# Heater_Control.net
KiCad netlist of a schematic drawn in Altium Designer
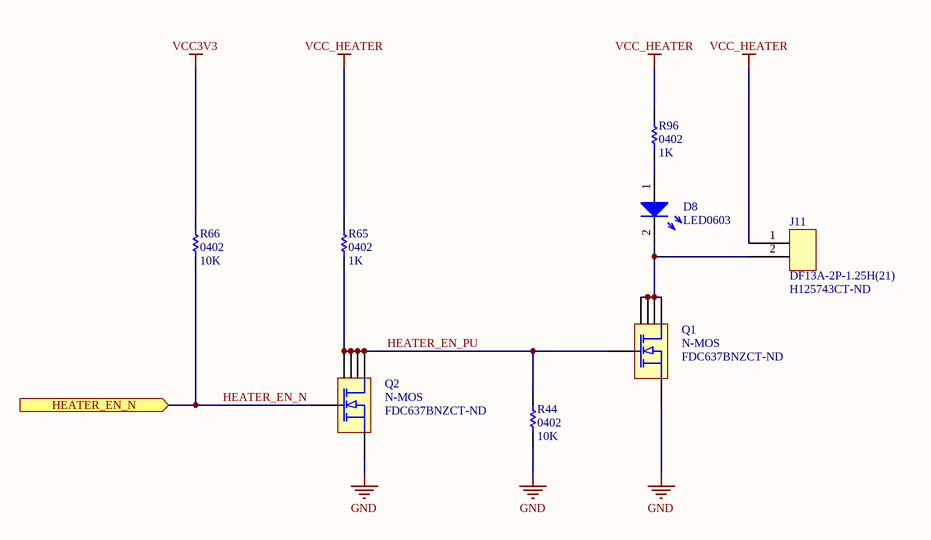
[diagram p0: Heater Control.SchDoc]

(export (version "E")
  (design (tool "Eeschema 10.0.6"))
  (components
    (comp (ref "D8")
      (value "LED0603")
      (footprint "LED0603")
      (description "Generic 0603 LED. Use ChipLED from Osram for generic ones.")
      (libsource (lib "heron-general") (part "LED0603"))
    )
    (comp (ref "J11")
      (value "DF13A-2P-1.25H(21)")
      (footprint "DF13A-2P-1.25H(21)")
      (description "2 pos DF13 right angle surface mount connector")
      (fields (field (name "SUPPLIER PART NUMBER 1") "H125743CT-ND"))
      (libsource (lib "DF13A-2P-1.25H(21)") (part "DF13A-2P-1.25H(21)"))
    )
    (comp (ref "Q1")
      (value "N-MOS")
      (footprint "SOT95P280X145-6N")
      (description "20V 6.2A, N-MOS, low gate on voltage")
      (fields (field (name "SUPPLIER PART NUMBER 1") "FDC637BNZCT-ND"))
      (libsource (lib "heron-general") (part "FDC637BNZCT-ND"))
    )
    (comp (ref "Q2")
      (value "N-MOS")
      (footprint "SOT95P280X145-6N")
      (description "20V 6.2A, N-MOS, low gate on voltage")
      (fields (field (name "SUPPLIER PART NUMBER 1") "FDC637BNZCT-ND"))
      (libsource (lib "heron-general") (part "FDC637BNZCT-ND"))
    )
    (comp (ref "R44")
      (value "0402")
      (footprint "RES0402R")
      (description "0402 resistor")
      (fields
        (field (name "ALTIUM_VALUE") "10K")
        (field (name "MANUFACTURER") "Panasonic")
        (field (name "MANUFACTURER PART NUMBER") "ERJ-2RKF1002X")
      )
      (libsource (lib "heron-general") (part "RES0402"))
    )
    (comp (ref "R65")
      (value "0402")
      (footprint "RES0402R")
      (description "0402 resistor")
      (fields (field (name "ALTIUM_VALUE") "1K"))
      (libsource (lib "RES0402") (part "RES0402"))
    )
    (comp (ref "R66")
      (value "0402")
      (footprint "RES0402R")
      (description "0402 resistor")
      (fields
        (field (name "ALTIUM_VALUE") "10K")
        (field (name "MANUFACTURER") "Panasonic")
        (field (name "MANUFACTURER PART NUMBER") "ERJ-2RKF1002X")
      )
      (libsource (lib "heron-general") (part "RES0402"))
    )
    (comp (ref "R96")
      (value "0402")
      (footprint "RES0402R")
      (description "0402 resistor")
      (fields (field (name "ALTIUM_VALUE") "1K"))
      (libsource (lib "RES0402") (part "RES0402"))
    )
  )
  (nets
    (net (code "1") (name "/HEATER_EN_N") (class "Default")
      (node (ref "Q2") (pin "3") (pinfunction "G_3") (pintype "passive"))
      (node (ref "R66") (pin "1") (pinfunction "1_1") (pintype "passive"))
    )
    (net (code "2") (name "/HEATER_EN_PU") (class "Default")
      (node (ref "Q1") (pin "3") (pinfunction "G_3") (pintype "passive"))
      (node (ref "Q2") (pin "1") (pinfunction "D_1") (pintype "passive"))
      (node (ref "Q2") (pin "2") (pinfunction "D_2") (pintype "passive"))
      (node (ref "Q2") (pin "5") (pinfunction "D_5") (pintype "passive"))
      (node (ref "Q2") (pin "6") (pinfunction "D_6") (pintype "passive"))
      (node (ref "R44") (pin "2") (pinfunction "2_2") (pintype "passive"))
      (node (ref "R65") (pin "1") (pinfunction "1_1") (pintype "passive"))
    )
    (net (code "3") (name "GND") (class "Default")
      (node (ref "Q1") (pin "4") (pinfunction "S_4") (pintype "passive"))
      (node (ref "Q2") (pin "4") (pinfunction "S_4") (pintype "passive"))
      (node (ref "R44") (pin "1") (pinfunction "1_1") (pintype "passive"))
    )
    (net (code "4") (name "Net-(D8-Pad1)") (class "Default")
      (node (ref "D8") (pin "1") (pinfunction "1_1") (pintype "passive"))
      (node (ref "R96") (pin "1") (pinfunction "1_1") (pintype "passive"))
    )
    (net (code "5") (name "Net-(D8-Pad2)") (class "Default")
      (node (ref "D8") (pin "2") (pinfunction "2_2") (pintype "passive"))
      (node (ref "J11") (pin "2") (pintype "passive"))
      (node (ref "Q1") (pin "1") (pinfunction "D_1") (pintype "passive"))
      (node (ref "Q1") (pin "2") (pinfunction "D_2") (pintype "passive"))
      (node (ref "Q1") (pin "5") (pinfunction "D_5") (pintype "passive"))
      (node (ref "Q1") (pin "6") (pinfunction "D_6") (pintype "passive"))
    )
    (net (code "6") (name "VCC3V3") (class "Default")
      (node (ref "R66") (pin "2") (pinfunction "2_2") (pintype "passive"))
    )
    (net (code "7") (name "VCC_HEATER") (class "Default")
      (node (ref "J11") (pin "1") (pintype "passive"))
      (node (ref "R65") (pin "2") (pinfunction "2_2") (pintype "passive"))
      (node (ref "R96") (pin "2") (pinfunction "2_2") (pintype "passive"))
    )
  )
)
